# e-Tapperhandpiece13.net
KiCad netlist of a schematic drawn in EAGLE
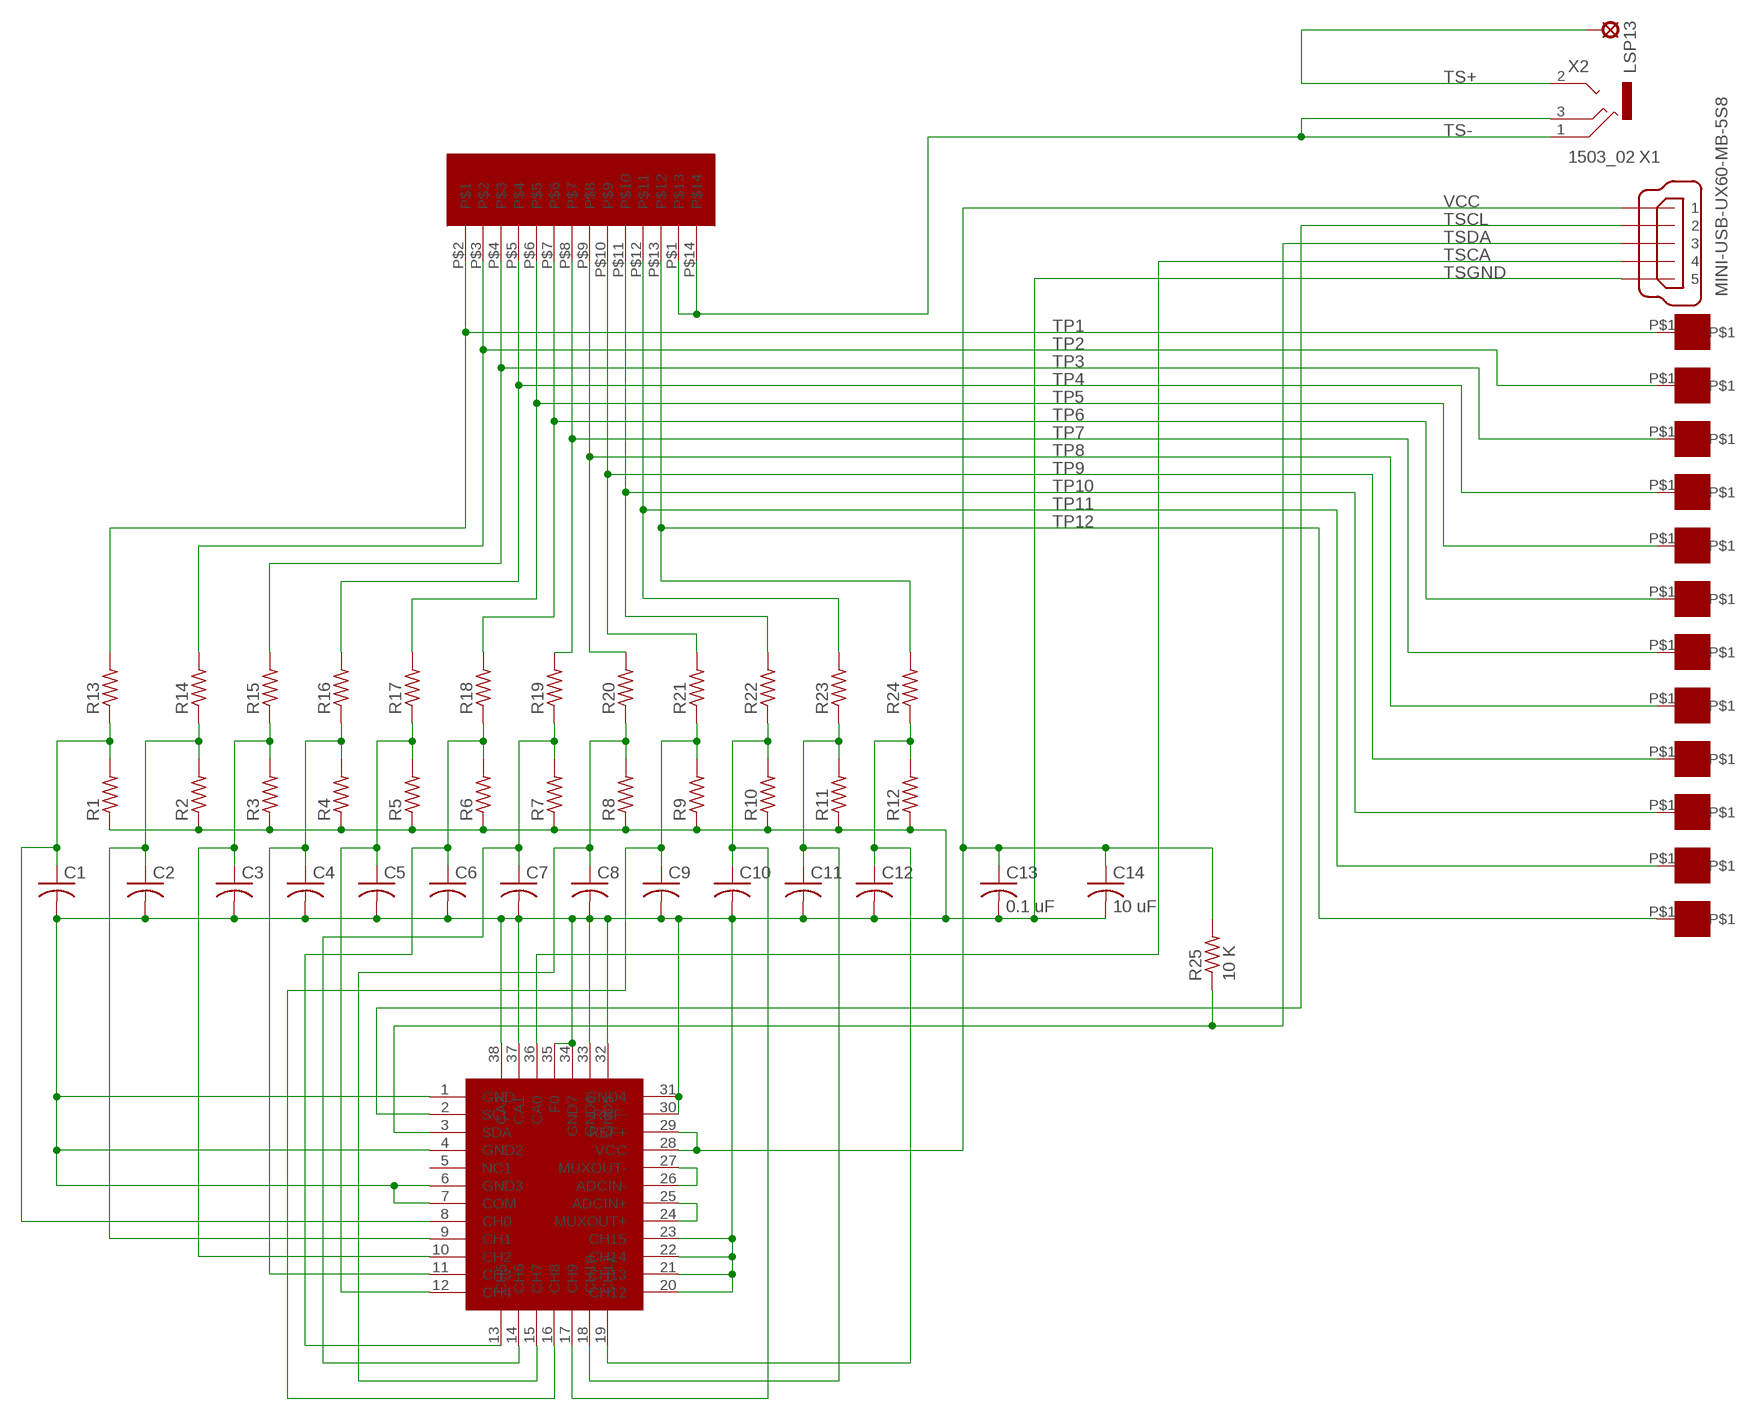
[diagram p0: schematic, sheet 1]

(export (version "E")
  (design (tool "Eeschema 10.0.6"))
  (components
    (comp (ref "C1")
      (value "C-USC0603")
      (footprint "eagle-import:C0603")
      (libsource (lib "eagle-import") (part "C-USC0603"))
    )
    (comp (ref "C2")
      (value "C-USC0603")
      (footprint "eagle-import:C0603")
      (libsource (lib "eagle-import") (part "C-USC0603"))
    )
    (comp (ref "C3")
      (value "C-USC0603")
      (footprint "eagle-import:C0603")
      (libsource (lib "eagle-import") (part "C-USC0603"))
    )
    (comp (ref "C4")
      (value "C-USC0603")
      (footprint "eagle-import:C0603")
      (libsource (lib "eagle-import") (part "C-USC0603"))
    )
    (comp (ref "C5")
      (value "C-USC0603")
      (footprint "eagle-import:C0603")
      (libsource (lib "eagle-import") (part "C-USC0603"))
    )
    (comp (ref "C6")
      (value "C-USC0603")
      (footprint "eagle-import:C0603")
      (libsource (lib "eagle-import") (part "C-USC0603"))
    )
    (comp (ref "C7")
      (value "C-USC0603")
      (footprint "eagle-import:C0603")
      (libsource (lib "eagle-import") (part "C-USC0603"))
    )
    (comp (ref "C8")
      (value "C-USC0603")
      (footprint "eagle-import:C0603")
      (libsource (lib "eagle-import") (part "C-USC0603"))
    )
    (comp (ref "C9")
      (value "C-USC0603")
      (footprint "eagle-import:C0603")
      (libsource (lib "eagle-import") (part "C-USC0603"))
    )
    (comp (ref "C10")
      (value "C-USC0603")
      (footprint "eagle-import:C0603")
      (libsource (lib "eagle-import") (part "C-USC0603"))
    )
    (comp (ref "C11")
      (value "C-USC0603")
      (footprint "eagle-import:C0603")
      (libsource (lib "eagle-import") (part "C-USC0603"))
    )
    (comp (ref "C12")
      (value "C-USC0603")
      (footprint "eagle-import:C0603")
      (libsource (lib "eagle-import") (part "C-USC0603"))
    )
    (comp (ref "C13")
      (value "0.1 uF")
      (footprint "eagle-import:C0603")
      (libsource (lib "eagle-import") (part "C-USC0603"))
    )
    (comp (ref "C14")
      (value "10 uF")
      (footprint "eagle-import:C0805")
      (libsource (lib "eagle-import") (part "C-USC0805"))
    )
    (comp (ref "LSP13")
      (value "SE11")
      (footprint "eagle-import:SE11")
      (libsource (lib "eagle-import") (part "SE11"))
    )
    (comp (ref "R1")
      (value "R-US_R0402")
      (footprint "eagle-import:R0402")
      (libsource (lib "eagle-import") (part "R-US_R0402"))
    )
    (comp (ref "R2")
      (value "R-US_R0402")
      (footprint "eagle-import:R0402")
      (libsource (lib "eagle-import") (part "R-US_R0402"))
    )
    (comp (ref "R3")
      (value "R-US_R0402")
      (footprint "eagle-import:R0402")
      (libsource (lib "eagle-import") (part "R-US_R0402"))
    )
    (comp (ref "R4")
      (value "R-US_R0402")
      (footprint "eagle-import:R0402")
      (libsource (lib "eagle-import") (part "R-US_R0402"))
    )
    (comp (ref "R5")
      (value "R-US_R0402")
      (footprint "eagle-import:R0402")
      (libsource (lib "eagle-import") (part "R-US_R0402"))
    )
    (comp (ref "R6")
      (value "R-US_R0402")
      (footprint "eagle-import:R0402")
      (libsource (lib "eagle-import") (part "R-US_R0402"))
    )
    (comp (ref "R7")
      (value "R-US_R0402")
      (footprint "eagle-import:R0402")
      (libsource (lib "eagle-import") (part "R-US_R0402"))
    )
    (comp (ref "R8")
      (value "R-US_R0402")
      (footprint "eagle-import:R0402")
      (libsource (lib "eagle-import") (part "R-US_R0402"))
    )
    (comp (ref "R9")
      (value "R-US_R0402")
      (footprint "eagle-import:R0402")
      (libsource (lib "eagle-import") (part "R-US_R0402"))
    )
    (comp (ref "R10")
      (value "R-US_R0402")
      (footprint "eagle-import:R0402")
      (libsource (lib "eagle-import") (part "R-US_R0402"))
    )
    (comp (ref "R11")
      (value "R-US_R0402")
      (footprint "eagle-import:R0402")
      (libsource (lib "eagle-import") (part "R-US_R0402"))
    )
    (comp (ref "R12")
      (value "R-US_R0402")
      (footprint "eagle-import:R0402")
      (libsource (lib "eagle-import") (part "R-US_R0402"))
    )
    (comp (ref "R13")
      (value "R-US_R0402")
      (footprint "eagle-import:R0402")
      (libsource (lib "eagle-import") (part "R-US_R0402"))
    )
    (comp (ref "R14")
      (value "R-US_R0402")
      (footprint "eagle-import:R0402")
      (libsource (lib "eagle-import") (part "R-US_R0402"))
    )
    (comp (ref "R15")
      (value "R-US_R0402")
      (footprint "eagle-import:R0402")
      (libsource (lib "eagle-import") (part "R-US_R0402"))
    )
    (comp (ref "R16")
      (value "R-US_R0402")
      (footprint "eagle-import:R0402")
      (libsource (lib "eagle-import") (part "R-US_R0402"))
    )
    (comp (ref "R17")
      (value "R-US_R0402")
      (footprint "eagle-import:R0402")
      (libsource (lib "eagle-import") (part "R-US_R0402"))
    )
    (comp (ref "R18")
      (value "R-US_R0402")
      (footprint "eagle-import:R0402")
      (libsource (lib "eagle-import") (part "R-US_R0402"))
    )
    (comp (ref "R19")
      (value "R-US_R0402")
      (footprint "eagle-import:R0402")
      (libsource (lib "eagle-import") (part "R-US_R0402"))
    )
    (comp (ref "R20")
      (value "R-US_R0402")
      (footprint "eagle-import:R0402")
      (libsource (lib "eagle-import") (part "R-US_R0402"))
    )
    (comp (ref "R21")
      (value "R-US_R0402")
      (footprint "eagle-import:R0402")
      (libsource (lib "eagle-import") (part "R-US_R0402"))
    )
    (comp (ref "R22")
      (value "R-US_R0402")
      (footprint "eagle-import:R0402")
      (libsource (lib "eagle-import") (part "R-US_R0402"))
    )
    (comp (ref "R23")
      (value "R-US_R0402")
      (footprint "eagle-import:R0402")
      (libsource (lib "eagle-import") (part "R-US_R0402"))
    )
    (comp (ref "R24")
      (value "R-US_R0402")
      (footprint "eagle-import:R0402")
      (libsource (lib "eagle-import") (part "R-US_R0402"))
    )
    (comp (ref "R25")
      (value "10 K")
      (footprint "eagle-import:R0402")
      (libsource (lib "eagle-import") (part "R-US_R0402"))
    )
    (comp (ref "TSP1")
      (value "ET1")
      (footprint "eagle-import:ET1")
      (libsource (lib "eagle-import") (part "ET1"))
    )
    (comp (ref "TSP2")
      (value "ET1")
      (footprint "eagle-import:ET1")
      (libsource (lib "eagle-import") (part "ET1"))
    )
    (comp (ref "TSP3")
      (value "ET1")
      (footprint "eagle-import:ET1")
      (libsource (lib "eagle-import") (part "ET1"))
    )
    (comp (ref "TSP4")
      (value "ET1")
      (footprint "eagle-import:ET1")
      (libsource (lib "eagle-import") (part "ET1"))
    )
    (comp (ref "TSP5")
      (value "ET1")
      (footprint "eagle-import:ET1")
      (libsource (lib "eagle-import") (part "ET1"))
    )
    (comp (ref "TSP6")
      (value "ET1")
      (footprint "eagle-import:ET1")
      (libsource (lib "eagle-import") (part "ET1"))
    )
    (comp (ref "TSP7")
      (value "ET1")
      (footprint "eagle-import:ET1")
      (libsource (lib "eagle-import") (part "ET1"))
    )
    (comp (ref "TSP8")
      (value "ET1")
      (footprint "eagle-import:ET1")
      (libsource (lib "eagle-import") (part "ET1"))
    )
    (comp (ref "TSP9")
      (value "ET1")
      (footprint "eagle-import:ET1")
      (libsource (lib "eagle-import") (part "ET1"))
    )
    (comp (ref "TSP10")
      (value "ET1")
      (footprint "eagle-import:ET1")
      (libsource (lib "eagle-import") (part "ET1"))
    )
    (comp (ref "TSP11")
      (value "ET1")
      (footprint "eagle-import:ET1")
      (libsource (lib "eagle-import") (part "ET1"))
    )
    (comp (ref "TSP12")
      (value "ET1")
      (footprint "eagle-import:ET1")
      (libsource (lib "eagle-import") (part "ET1"))
    )
    (comp (ref "U$1")
      (value "LTC2497")
      (footprint "eagle-import:QFN38-5X7")
      (libsource (lib "eagle-import") (part "LTC2497"))
    )
    (comp (ref "U$2")
      (value "SS112D01")
      (footprint "eagle-import:SS112D01")
      (libsource (lib "eagle-import") (part "SS112D01"))
    )
    (comp (ref "X1")
      (value "MINI-USB-UX60-MB-5S8")
      (footprint "eagle-import:UX60-MB-5S8")
      (libsource (lib "eagle-import") (part "MINI-USB-UX60-MB-5S8"))
    )
    (comp (ref "X2")
      (value "1503_02")
      (footprint "eagle-import:1503_02")
      (libsource (lib "eagle-import") (part "1503_02"))
    )
  )
  (nets
    (net (code "1") (name "/TP1") (class "Default")
      (node (ref "R13") (pin "2") (pinfunction "2_2") (pintype "passive"))
      (node (ref "TSP1") (pin "P$1") (pinfunction "P$1_P$1") (pintype "bidirectional"))
      (node (ref "U$2") (pin "P$2") (pinfunction "P$1_P$2") (pintype "bidirectional"))
    )
    (net (code "2") (name "/TP2") (class "Default")
      (node (ref "R14") (pin "2") (pinfunction "2_2") (pintype "passive"))
      (node (ref "TSP2") (pin "P$1") (pinfunction "P$1_P$1") (pintype "bidirectional"))
      (node (ref "U$2") (pin "P$3") (pinfunction "P$2_P$3") (pintype "bidirectional"))
    )
    (net (code "3") (name "/TP3") (class "Default")
      (node (ref "R15") (pin "2") (pinfunction "2_2") (pintype "passive"))
      (node (ref "TSP3") (pin "P$1") (pinfunction "P$1_P$1") (pintype "bidirectional"))
      (node (ref "U$2") (pin "P$4") (pinfunction "P$3_P$4") (pintype "bidirectional"))
    )
    (net (code "4") (name "/TP4") (class "Default")
      (node (ref "R16") (pin "2") (pinfunction "2_2") (pintype "passive"))
      (node (ref "TSP4") (pin "P$1") (pinfunction "P$1_P$1") (pintype "bidirectional"))
      (node (ref "U$2") (pin "P$5") (pinfunction "P$4_P$5") (pintype "bidirectional"))
    )
    (net (code "5") (name "/TP5") (class "Default")
      (node (ref "R17") (pin "2") (pinfunction "2_2") (pintype "passive"))
      (node (ref "TSP5") (pin "P$1") (pinfunction "P$1_P$1") (pintype "bidirectional"))
      (node (ref "U$2") (pin "P$6") (pinfunction "P$5_P$6") (pintype "bidirectional"))
    )
    (net (code "6") (name "/TP6") (class "Default")
      (node (ref "R18") (pin "2") (pinfunction "2_2") (pintype "passive"))
      (node (ref "TSP6") (pin "P$1") (pinfunction "P$1_P$1") (pintype "bidirectional"))
      (node (ref "U$2") (pin "P$7") (pinfunction "P$6_P$7") (pintype "bidirectional"))
    )
    (net (code "7") (name "/TP7") (class "Default")
      (node (ref "R19") (pin "2") (pinfunction "2_2") (pintype "passive"))
      (node (ref "TSP7") (pin "P$1") (pinfunction "P$1_P$1") (pintype "bidirectional"))
      (node (ref "U$2") (pin "P$8") (pinfunction "P$7_P$8") (pintype "bidirectional"))
    )
    (net (code "8") (name "/TP8") (class "Default")
      (node (ref "R20") (pin "2") (pinfunction "2_2") (pintype "passive"))
      (node (ref "TSP8") (pin "P$1") (pinfunction "P$1_P$1") (pintype "bidirectional"))
      (node (ref "U$2") (pin "P$9") (pinfunction "P$8_P$9") (pintype "bidirectional"))
    )
    (net (code "9") (name "/TP9") (class "Default")
      (node (ref "R21") (pin "2") (pinfunction "2_2") (pintype "passive"))
      (node (ref "TSP9") (pin "P$1") (pinfunction "P$1_P$1") (pintype "bidirectional"))
      (node (ref "U$2") (pin "P$10") (pinfunction "P$9_P$10") (pintype "bidirectional"))
    )
    (net (code "10") (name "/TP10") (class "Default")
      (node (ref "R22") (pin "2") (pinfunction "2_2") (pintype "passive"))
      (node (ref "TSP10") (pin "P$1") (pinfunction "P$1_P$1") (pintype "bidirectional"))
      (node (ref "U$2") (pin "P$11") (pinfunction "P$10_P$11") (pintype "bidirectional"))
    )
    (net (code "11") (name "/TP11") (class "Default")
      (node (ref "R23") (pin "2") (pinfunction "2_2") (pintype "passive"))
      (node (ref "TSP11") (pin "P$1") (pinfunction "P$1_P$1") (pintype "bidirectional"))
      (node (ref "U$2") (pin "P$12") (pinfunction "P$11_P$12") (pintype "bidirectional"))
    )
    (net (code "12") (name "/TP12") (class "Default")
      (node (ref "R24") (pin "2") (pinfunction "2_2") (pintype "passive"))
      (node (ref "TSP12") (pin "P$1") (pinfunction "P$1_P$1") (pintype "bidirectional"))
      (node (ref "U$2") (pin "P$13") (pinfunction "P$12_P$13") (pintype "bidirectional"))
    )
    (net (code "13") (name "/TS+") (class "Default")
      (node (ref "LSP13") (pin "MP") (pinfunction "MP_MP") (pintype "passive"))
      (node (ref "X2") (pin "2") (pinfunction "2_2") (pintype "passive"))
    )
    (net (code "14") (name "/TS-") (class "Default")
      (node (ref "U$2") (pin "P$1") (pinfunction "P$13_P$1") (pintype "bidirectional"))
      (node (ref "U$2") (pin "P$14") (pinfunction "P$14_P$14") (pintype "bidirectional"))
      (node (ref "X2") (pin "1") (pinfunction "1_1") (pintype "passive"))
      (node (ref "X2") (pin "3") (pinfunction "3_3") (pintype "passive"))
    )
    (net (code "15") (name "/TSCA") (class "Default")
      (node (ref "U$1") (pin "36") (pinfunction "CA0_36") (pintype "bidirectional"))
      (node (ref "X1") (pin "4") (pinfunction "4_4") (pintype "input"))
    )
    (net (code "16") (name "/TSCL") (class "Default")
      (node (ref "U$1") (pin "2") (pinfunction "SCL_2") (pintype "bidirectional"))
      (node (ref "X1") (pin "2") (pinfunction "2_2") (pintype "input"))
    )
    (net (code "17") (name "/TSDA") (class "Default")
      (node (ref "R25") (pin "1") (pinfunction "1_1") (pintype "passive"))
      (node (ref "U$1") (pin "3") (pinfunction "SDA_3") (pintype "bidirectional"))
      (node (ref "X1") (pin "3") (pinfunction "3_3") (pintype "input"))
    )
    (net (code "18") (name "/TSGND") (class "Default")
      (node (ref "C1") (pin "2") (pinfunction "2_2") (pintype "passive"))
      (node (ref "C10") (pin "2") (pinfunction "2_2") (pintype "passive"))
      (node (ref "C11") (pin "2") (pinfunction "2_2") (pintype "passive"))
      (node (ref "C12") (pin "2") (pinfunction "2_2") (pintype "passive"))
      (node (ref "C13") (pin "2") (pinfunction "2_2") (pintype "passive"))
      (node (ref "C14") (pin "2") (pinfunction "2_2") (pintype "passive"))
      (node (ref "C2") (pin "2") (pinfunction "2_2") (pintype "passive"))
      (node (ref "C3") (pin "2") (pinfunction "2_2") (pintype "passive"))
      (node (ref "C4") (pin "2") (pinfunction "2_2") (pintype "passive"))
      (node (ref "C5") (pin "2") (pinfunction "2_2") (pintype "passive"))
      (node (ref "C6") (pin "2") (pinfunction "2_2") (pintype "passive"))
      (node (ref "C7") (pin "2") (pinfunction "2_2") (pintype "passive"))
      (node (ref "C8") (pin "2") (pinfunction "2_2") (pintype "passive"))
      (node (ref "C9") (pin "2") (pinfunction "2_2") (pintype "passive"))
      (node (ref "R1") (pin "1") (pinfunction "1_1") (pintype "passive"))
      (node (ref "R10") (pin "1") (pinfunction "1_1") (pintype "passive"))
      (node (ref "R11") (pin "1") (pinfunction "1_1") (pintype "passive"))
      (node (ref "R12") (pin "1") (pinfunction "1_1") (pintype "passive"))
      (node (ref "R2") (pin "1") (pinfunction "1_1") (pintype "passive"))
      (node (ref "R3") (pin "1") (pinfunction "1_1") (pintype "passive"))
      (node (ref "R4") (pin "1") (pinfunction "1_1") (pintype "passive"))
      (node (ref "R5") (pin "1") (pinfunction "1_1") (pintype "passive"))
      (node (ref "R6") (pin "1") (pinfunction "1_1") (pintype "passive"))
      (node (ref "R7") (pin "1") (pinfunction "1_1") (pintype "passive"))
      (node (ref "R8") (pin "1") (pinfunction "1_1") (pintype "passive"))
      (node (ref "R9") (pin "1") (pinfunction "1_1") (pintype "passive"))
      (node (ref "U$1") (pin "1") (pinfunction "GND_1") (pintype "power_in"))
      (node (ref "U$1") (pin "20") (pinfunction "CH12_20") (pintype "input"))
      (node (ref "U$1") (pin "21") (pinfunction "CH13_21") (pintype "input"))
      (node (ref "U$1") (pin "22") (pinfunction "CH14_22") (pintype "input"))
      (node (ref "U$1") (pin "23") (pinfunction "CH15_23") (pintype "input"))
      (node (ref "U$1") (pin "30") (pinfunction "REF-_30") (pintype "bidirectional"))
      (node (ref "U$1") (pin "31") (pinfunction "GND4_31") (pintype "power_in"))
      (node (ref "U$1") (pin "32") (pinfunction "GND5_32") (pintype "power_in"))
      (node (ref "U$1") (pin "33") (pinfunction "GND6_33") (pintype "power_in"))
      (node (ref "U$1") (pin "34") (pinfunction "GND7_34") (pintype "power_in"))
      (node (ref "U$1") (pin "35") (pinfunction "F0_35") (pintype "bidirectional"))
      (node (ref "U$1") (pin "37") (pinfunction "CA1_37") (pintype "bidirectional"))
      (node (ref "U$1") (pin "38") (pinfunction "CA2_38") (pintype "bidirectional"))
      (node (ref "U$1") (pin "4") (pinfunction "GND2_4") (pintype "power_in"))
      (node (ref "U$1") (pin "6") (pinfunction "GND3_6") (pintype "power_in"))
      (node (ref "U$1") (pin "7") (pinfunction "COM_7") (pintype "power_in"))
      (node (ref "X1") (pin "5") (pinfunction "5_5") (pintype "input"))
    )
    (net (code "19") (name "/VCC") (class "Default")
      (node (ref "C13") (pin "1") (pinfunction "1_1") (pintype "passive"))
      (node (ref "C14") (pin "1") (pinfunction "1_1") (pintype "passive"))
      (node (ref "R25") (pin "2") (pinfunction "2_2") (pintype "passive"))
      (node (ref "U$1") (pin "28") (pinfunction "VCC_28") (pintype "power_in"))
      (node (ref "U$1") (pin "29") (pinfunction "REF+_29") (pintype "bidirectional"))
      (node (ref "X1") (pin "1") (pinfunction "1_1") (pintype "input"))
    )
    (net (code "20") (name "Net-(U$1-ADCIN+)") (class "Default")
      (node (ref "U$1") (pin "24") (pinfunction "MUXOUT+_24") (pintype "bidirectional"))
      (node (ref "U$1") (pin "25") (pinfunction "ADCIN+_25") (pintype "bidirectional"))
    )
    (net (code "21") (name "Net-(U$1-ADCIN-)") (class "Default")
      (node (ref "U$1") (pin "26") (pinfunction "ADCIN-_26") (pintype "bidirectional"))
      (node (ref "U$1") (pin "27") (pinfunction "MUXOUT-_27") (pintype "bidirectional"))
    )
    (net (code "22") (name "Net-(U$1-CH0)") (class "Default")
      (node (ref "C1") (pin "1") (pinfunction "1_1") (pintype "passive"))
      (node (ref "R1") (pin "2") (pinfunction "2_2") (pintype "passive"))
      (node (ref "R13") (pin "1") (pinfunction "1_1") (pintype "passive"))
      (node (ref "U$1") (pin "8") (pinfunction "CH0_8") (pintype "input"))
    )
    (net (code "23") (name "Net-(U$1-CH1)") (class "Default")
      (node (ref "C2") (pin "1") (pinfunction "1_1") (pintype "passive"))
      (node (ref "R14") (pin "1") (pinfunction "1_1") (pintype "passive"))
      (node (ref "R2") (pin "2") (pinfunction "2_2") (pintype "passive"))
      (node (ref "U$1") (pin "9") (pinfunction "CH1_9") (pintype "input"))
    )
    (net (code "24") (name "Net-(U$1-CH2)") (class "Default")
      (node (ref "C3") (pin "1") (pinfunction "1_1") (pintype "passive"))
      (node (ref "R15") (pin "1") (pinfunction "1_1") (pintype "passive"))
      (node (ref "R3") (pin "2") (pinfunction "2_2") (pintype "passive"))
      (node (ref "U$1") (pin "10") (pinfunction "CH2_10") (pintype "input"))
    )
    (net (code "25") (name "Net-(U$1-CH3)") (class "Default")
      (node (ref "C4") (pin "1") (pinfunction "1_1") (pintype "passive"))
      (node (ref "R16") (pin "1") (pinfunction "1_1") (pintype "passive"))
      (node (ref "R4") (pin "2") (pinfunction "2_2") (pintype "passive"))
      (node (ref "U$1") (pin "11") (pinfunction "CH3_11") (pintype "input"))
    )
    (net (code "26") (name "Net-(U$1-CH4)") (class "Default")
      (node (ref "C5") (pin "1") (pinfunction "1_1") (pintype "passive"))
      (node (ref "R17") (pin "1") (pinfunction "1_1") (pintype "passive"))
      (node (ref "R5") (pin "2") (pinfunction "2_2") (pintype "passive"))
      (node (ref "U$1") (pin "12") (pinfunction "CH4_12") (pintype "input"))
    )
    (net (code "27") (name "Net-(U$1-CH5)") (class "Default")
      (node (ref "C6") (pin "1") (pinfunction "1_1") (pintype "passive"))
      (node (ref "R18") (pin "1") (pinfunction "1_1") (pintype "passive"))
      (node (ref "R6") (pin "2") (pinfunction "2_2") (pintype "passive"))
      (node (ref "U$1") (pin "13") (pinfunction "CH5_13") (pintype "input"))
    )
    (net (code "28") (name "Net-(U$1-CH6)") (class "Default")
      (node (ref "C7") (pin "1") (pinfunction "1_1") (pintype "passive"))
      (node (ref "R19") (pin "1") (pinfunction "1_1") (pintype "passive"))
      (node (ref "R7") (pin "2") (pinfunction "2_2") (pintype "passive"))
      (node (ref "U$1") (pin "14") (pinfunction "CH6_14") (pintype "input"))
    )
    (net (code "29") (name "Net-(U$1-CH7)") (class "Default")
      (node (ref "C8") (pin "1") (pinfunction "1_1") (pintype "passive"))
      (node (ref "R20") (pin "1") (pinfunction "1_1") (pintype "passive"))
      (node (ref "R8") (pin "2") (pinfunction "2_2") (pintype "passive"))
      (node (ref "U$1") (pin "15") (pinfunction "CH7_15") (pintype "input"))
    )
    (net (code "30") (name "Net-(U$1-CH8)") (class "Default")
      (node (ref "C9") (pin "1") (pinfunction "1_1") (pintype "passive"))
      (node (ref "R21") (pin "1") (pinfunction "1_1") (pintype "passive"))
      (node (ref "R9") (pin "2") (pinfunction "2_2") (pintype "passive"))
      (node (ref "U$1") (pin "16") (pinfunction "CH8_16") (pintype "input"))
    )
    (net (code "31") (name "Net-(U$1-CH9)") (class "Default")
      (node (ref "C10") (pin "1") (pinfunction "1_1") (pintype "passive"))
      (node (ref "R10") (pin "2") (pinfunction "2_2") (pintype "passive"))
      (node (ref "R22") (pin "1") (pinfunction "1_1") (pintype "passive"))
      (node (ref "U$1") (pin "17") (pinfunction "CH9_17") (pintype "input"))
    )
    (net (code "32") (name "Net-(U$1-CH10)") (class "Default")
      (node (ref "C11") (pin "1") (pinfunction "1_1") (pintype "passive"))
      (node (ref "R11") (pin "2") (pinfunction "2_2") (pintype "passive"))
      (node (ref "R23") (pin "1") (pinfunction "1_1") (pintype "passive"))
      (node (ref "U$1") (pin "18") (pinfunction "CH10_18") (pintype "input"))
    )
    (net (code "33") (name "Net-(U$1-CH11)") (class "Default")
      (node (ref "C12") (pin "1") (pinfunction "1_1") (pintype "passive"))
      (node (ref "R12") (pin "2") (pinfunction "2_2") (pintype "passive"))
      (node (ref "R24") (pin "1") (pinfunction "1_1") (pintype "passive"))
      (node (ref "U$1") (pin "19") (pinfunction "CH11_19") (pintype "input"))
    )
    (net (code "34") (name "unconnected-(U$1-NC1-Pad5)") (class "Default")
      (node (ref "U$1") (pin "5") (pinfunction "NC1_5") (pintype "no_connect"))
    )
    (net (code "35") (name "unconnected-(X2-2-Pad2@2)") (class "Default")
      (node (ref "X2") (pin "2@2") (pinfunction "2_2@2") (pintype "passive"))
    )
  )
)
